# Untitled.net
KiCad netlist of a schematic drawn in EAGLE
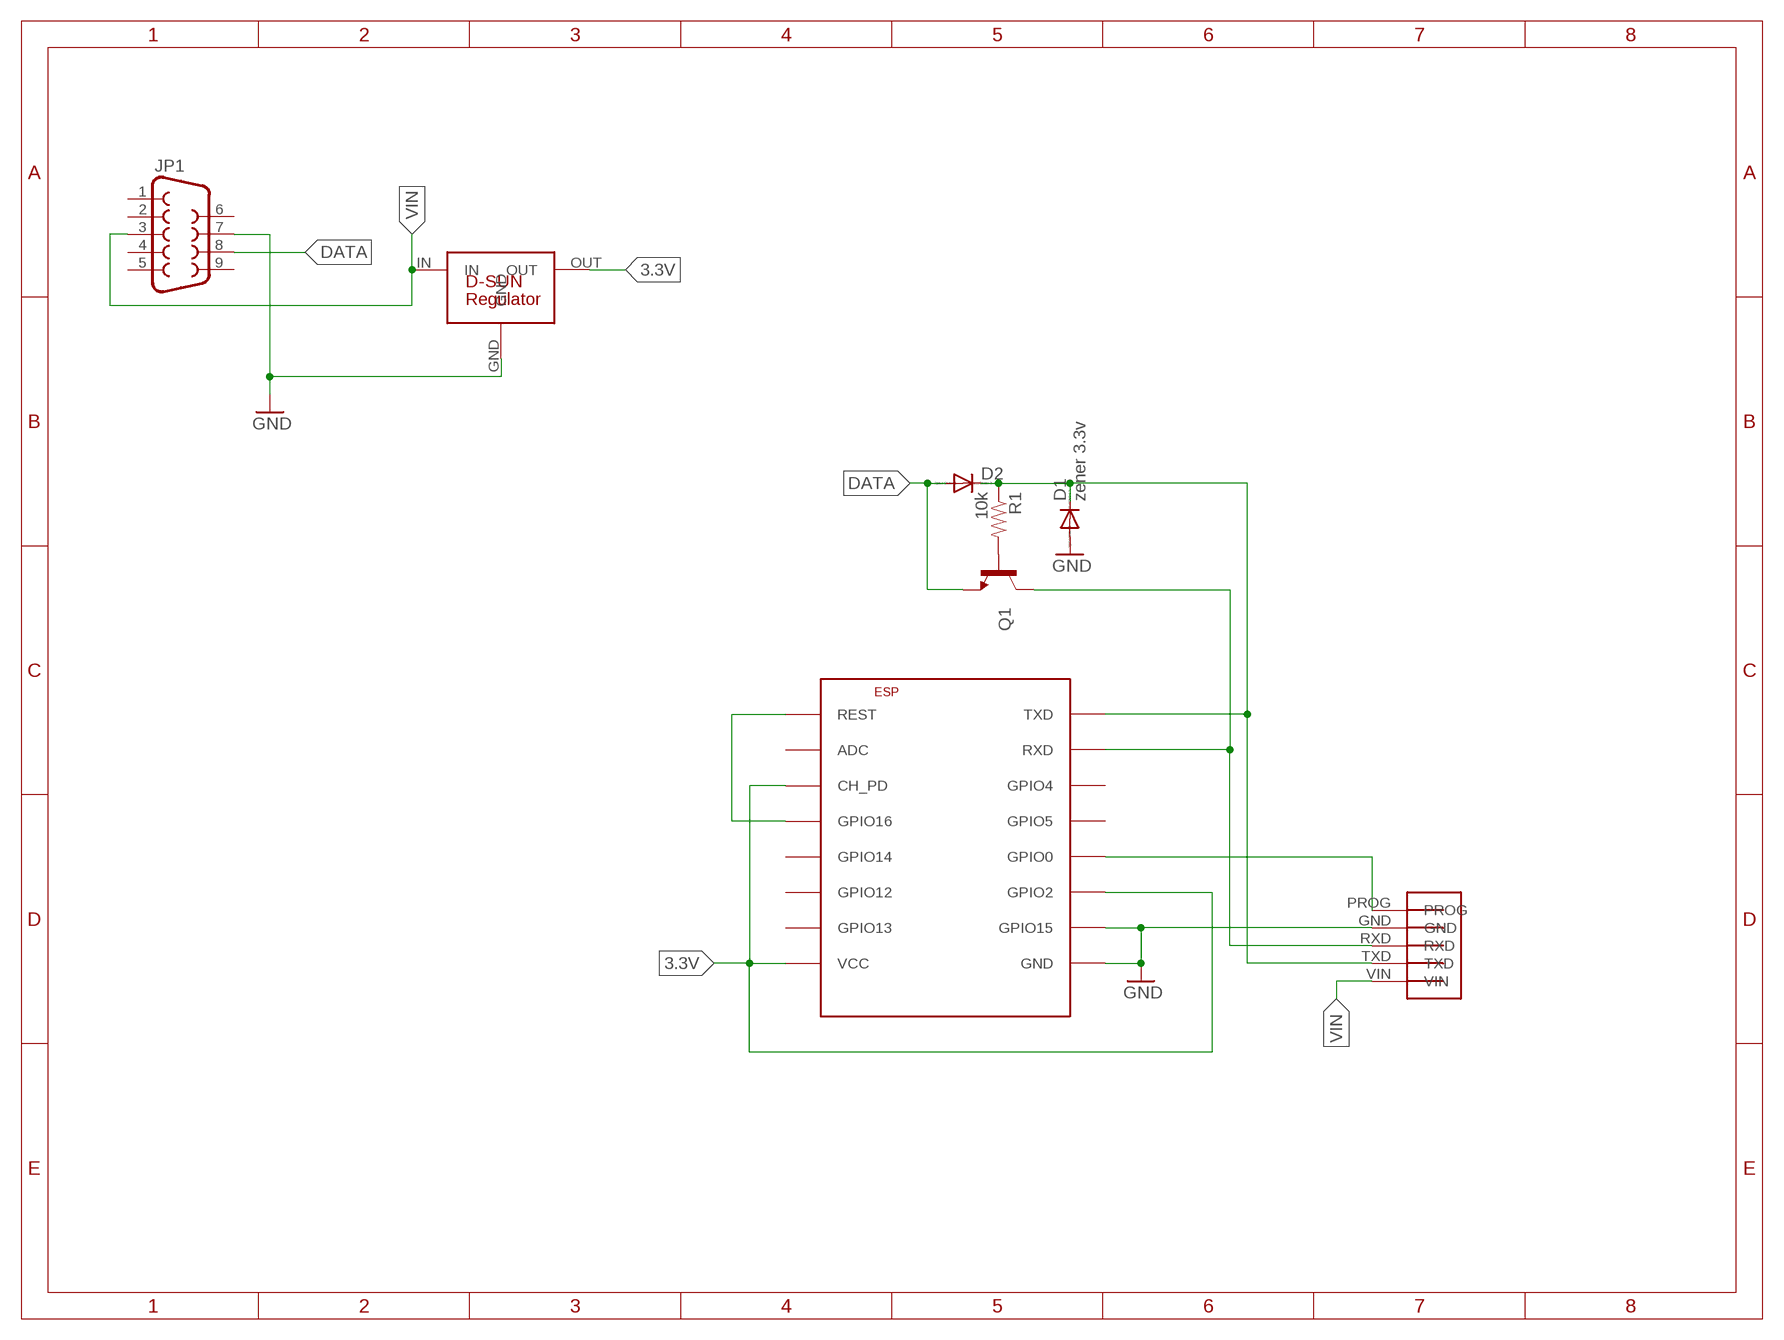
[diagram p0: schematic, sheet 1]

(export (version "E")
  (design (tool "Eeschema 10.0.6"))
  (components
    (comp (ref "D1")
      (value "zener 3.3v")
      (footprint "eagle-import:MINIMELF")
      (libsource (lib "eagle-import") (part "DIODE-MINIMELF"))
    )
    (comp (ref "D2")
      (value "DIODE-MINIMELF")
      (footprint "eagle-import:MINIMELF")
      (libsource (lib "eagle-import") (part "DIODE-MINIMELF"))
    )
    (comp (ref "ESP")
      (value "ESP8266-07")
      (footprint "eagle-import:ESP-07")
      (libsource (lib "eagle-import") (part "ESP8266-07"))
    )
    (comp (ref "JP1")
      (value "DB9MALE")
      (footprint "eagle-import:DB9_MALE")
      (libsource (lib "eagle-import") (part "DB9MALE"))
    )
    (comp (ref "Q1")
      (value "TRANSISTOR_NPNSOT23-3")
      (footprint "eagle-import:SOT23-3")
      (libsource (lib "eagle-import") (part "TRANSISTOR_NPNSOT23-3"))
    )
    (comp (ref "R1")
      (value "10k")
      (footprint "eagle-import:0805")
      (libsource (lib "eagle-import") (part "RESISTOR0805-RES"))
    )
    (comp (ref "U$3")
      (value "ESPROG")
      (footprint "eagle-import:ESPROG")
      (libsource (lib "eagle-import") (part "ESPROG"))
    )
    (comp (ref "U$4")
      (value "D-SUN-REG")
      (footprint "eagle-import:D-SUN-REG")
      (libsource (lib "eagle-import") (part "D-SUN-REG"))
    )
  )
  (nets
    (net (code "1") (name "3.3V") (class "Default")
      (node (ref "ESP") (pin "CH_PD") (pinfunction "CH_PD_CH_PD") (pintype "input"))
      (node (ref "ESP") (pin "GPIO2") (pinfunction "GPIO2_GPIO2") (pintype "bidirectional"))
      (node (ref "ESP") (pin "VCC") (pinfunction "VCC_VCC") (pintype "power_in"))
      (node (ref "U$4") (pin "OUT") (pinfunction "OUT_OUT") (pintype "bidirectional"))
    )
    (net (code "2") (name "DATA") (class "Default")
      (node (ref "D2") (pin "A") (pinfunction "A_A") (pintype "passive"))
      (node (ref "JP1") (pin "8") (pinfunction "8_8") (pintype "passive"))
      (node (ref "Q1") (pin "2") (pinfunction "E_2") (pintype "passive"))
    )
    (net (code "3") (name "GND") (class "Default")
      (node (ref "D1") (pin "A") (pinfunction "A_A") (pintype "passive"))
      (node (ref "ESP") (pin "GND") (pinfunction "GND_GND") (pintype "power_in"))
      (node (ref "ESP") (pin "GPIO15") (pinfunction "GPIO15_GPIO15") (pintype "input"))
      (node (ref "JP1") (pin "7") (pinfunction "7_7") (pintype "passive"))
      (node (ref "U$3") (pin "GND") (pinfunction "GND_GND") (pintype "bidirectional"))
      (node (ref "U$4") (pin "GND") (pinfunction "GND_GND") (pintype "bidirectional"))
    )
    (net (code "4") (name "Net-(D1-PadC)") (class "Default")
      (node (ref "D1") (pin "C") (pinfunction "C_C") (pintype "passive"))
      (node (ref "D2") (pin "C") (pinfunction "C_C") (pintype "passive"))
      (node (ref "ESP") (pin "TXD") (pinfunction "TXD_TXD") (pintype "output"))
      (node (ref "R1") (pin "1") (pinfunction "1_1") (pintype "passive"))
      (node (ref "U$3") (pin "TXD") (pinfunction "TXD_TXD") (pintype "bidirectional"))
    )
    (net (code "5") (name "Net-(ESP-PadGPIO0)") (class "Default")
      (node (ref "ESP") (pin "GPIO0") (pinfunction "GPIO0_GPIO0") (pintype "bidirectional"))
      (node (ref "U$3") (pin "PROG") (pinfunction "PROG_PROG") (pintype "bidirectional"))
    )
    (net (code "6") (name "Net-(ESP-PadGPIO16)") (class "Default")
      (node (ref "ESP") (pin "GPIO16") (pinfunction "GPIO16_GPIO16") (pintype "bidirectional"))
      (node (ref "ESP") (pin "REST") (pinfunction "REST_REST") (pintype "bidirectional"))
    )
    (net (code "7") (name "Net-(Q1-B)") (class "Default")
      (node (ref "Q1") (pin "1") (pinfunction "B_1") (pintype "passive"))
      (node (ref "R1") (pin "2") (pinfunction "2_2") (pintype "passive"))
    )
    (net (code "8") (name "Net-(Q1-C)") (class "Default")
      (node (ref "ESP") (pin "RXD") (pinfunction "RXD_RXD") (pintype "input"))
      (node (ref "Q1") (pin "3") (pinfunction "C_3") (pintype "passive"))
      (node (ref "U$3") (pin "RXD") (pinfunction "RXD_RXD") (pintype "bidirectional"))
    )
    (net (code "9") (name "VIN") (class "Default")
      (node (ref "JP1") (pin "3") (pinfunction "3_3") (pintype "passive"))
      (node (ref "U$3") (pin "VIN") (pinfunction "VIN_VIN") (pintype "bidirectional"))
      (node (ref "U$4") (pin "IN") (pinfunction "IN_IN") (pintype "bidirectional"))
    )
    (net (code "10") (name "unconnected-(ESP-PadADC)") (class "Default")
      (node (ref "ESP") (pin "ADC") (pinfunction "ADC_ADC") (pintype "bidirectional"))
    )
    (net (code "11") (name "unconnected-(ESP-PadGPIO4)") (class "Default")
      (node (ref "ESP") (pin "GPIO4") (pinfunction "GPIO4_GPIO4") (pintype "bidirectional"))
    )
    (net (code "12") (name "unconnected-(ESP-PadGPIO5)") (class "Default")
      (node (ref "ESP") (pin "GPIO5") (pinfunction "GPIO5_GPIO5") (pintype "bidirectional"))
    )
    (net (code "13") (name "unconnected-(ESP-PadGPIO12)") (class "Default")
      (node (ref "ESP") (pin "GPIO12") (pinfunction "GPIO12_GPIO12") (pintype "bidirectional"))
    )
    (net (code "14") (name "unconnected-(ESP-PadGPIO13)") (class "Default")
      (node (ref "ESP") (pin "GPIO13") (pinfunction "GPIO13_GPIO13") (pintype "bidirectional"))
    )
    (net (code "15") (name "unconnected-(ESP-PadGPIO14)") (class "Default")
      (node (ref "ESP") (pin "GPIO14") (pinfunction "GPIO14_GPIO14") (pintype "bidirectional"))
    )
    (net (code "16") (name "unconnected-(JP1-Pad1)") (class "Default")
      (node (ref "JP1") (pin "1") (pinfunction "1_1") (pintype "passive"))
    )
    (net (code "17") (name "unconnected-(JP1-Pad2)") (class "Default")
      (node (ref "JP1") (pin "2") (pinfunction "2_2") (pintype "passive"))
    )
    (net (code "18") (name "unconnected-(JP1-Pad4)") (class "Default")
      (node (ref "JP1") (pin "4") (pinfunction "4_4") (pintype "passive"))
    )
    (net (code "19") (name "unconnected-(JP1-Pad5)") (class "Default")
      (node (ref "JP1") (pin "5") (pinfunction "5_5") (pintype "passive"))
    )
    (net (code "20") (name "unconnected-(JP1-Pad6)") (class "Default")
      (node (ref "JP1") (pin "6") (pinfunction "6_6") (pintype "passive"))
    )
    (net (code "21") (name "unconnected-(JP1-Pad9)") (class "Default")
      (node (ref "JP1") (pin "9") (pinfunction "9_9") (pintype "passive"))
    )
  )
)
